# 5_SDRAM.net
KiCad netlist of a schematic drawn in Altium Designer
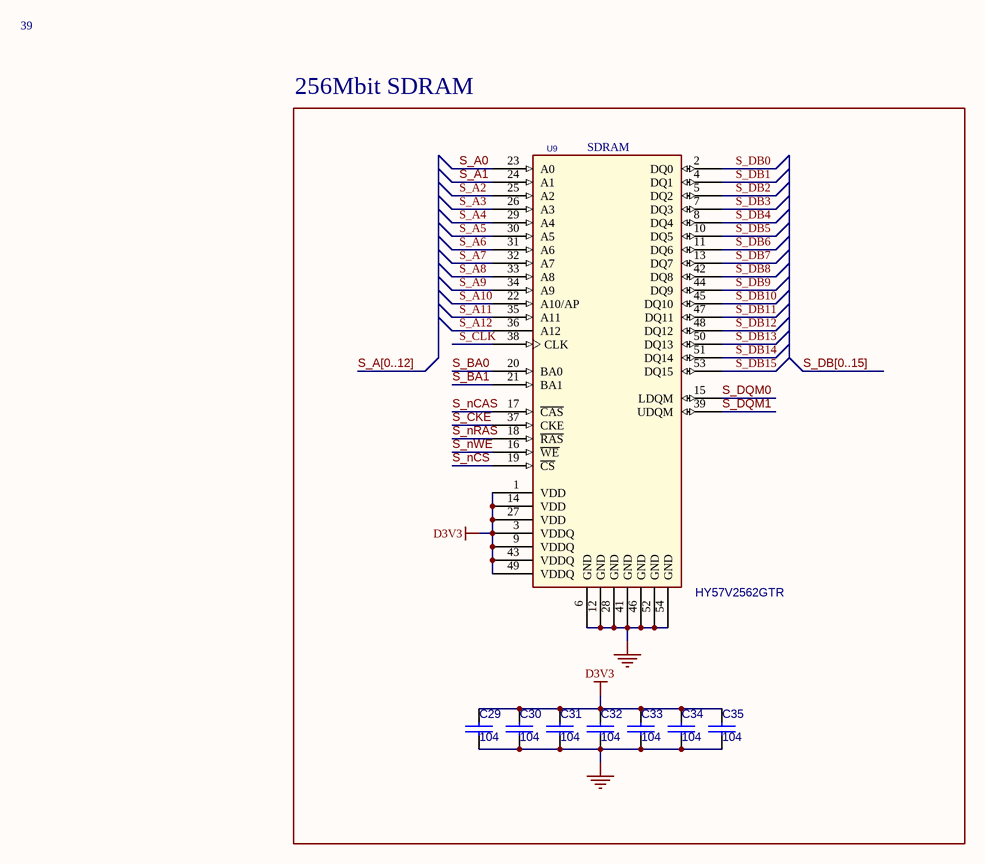
[diagram p0: 5_SDRAM.SchDoc]

(export (version "E")
  (design (tool "Eeschema 10.0.6"))
  (components
    (comp (ref "C29") (value "104") (libsource (lib "*") (part "C_Dup2")))
    (comp (ref "C30") (value "104") (libsource (lib "*") (part "C_Dup2")))
    (comp (ref "C31") (value "104") (libsource (lib "*") (part "C_Dup2")))
    (comp (ref "C32") (value "104") (libsource (lib "*") (part "C_Dup2")))
    (comp (ref "C33") (value "104") (libsource (lib "*") (part "C_Dup2")))
    (comp (ref "C34") (value "104") (libsource (lib "*") (part "C_Dup2")))
    (comp (ref "C35") (value "104") (libsource (lib "*") (part "C_Dup2")))
    (comp (ref "U9") (value "HY57V2562GTR") (libsource (lib "*") (part "HY57651620/SO_0")))
  )
  (nets
    (net (code "1") (name "/S_A0") (class "Default")
      (node (ref "U9") (pin "23") (pinfunction "A0_23") (pintype "input"))
    )
    (net (code "2") (name "/S_A1") (class "Default")
      (node (ref "U9") (pin "24") (pinfunction "A1_24") (pintype "input"))
    )
    (net (code "3") (name "/S_A2") (class "Default")
      (node (ref "U9") (pin "25") (pinfunction "A2_25") (pintype "input"))
    )
    (net (code "4") (name "/S_A3") (class "Default")
      (node (ref "U9") (pin "26") (pinfunction "A3_26") (pintype "input"))
    )
    (net (code "5") (name "/S_A4") (class "Default")
      (node (ref "U9") (pin "29") (pinfunction "A4_29") (pintype "input"))
    )
    (net (code "6") (name "/S_A5") (class "Default")
      (node (ref "U9") (pin "30") (pinfunction "A5_30") (pintype "input"))
    )
    (net (code "7") (name "/S_A6") (class "Default")
      (node (ref "U9") (pin "31") (pinfunction "A6_31") (pintype "input"))
    )
    (net (code "8") (name "/S_A7") (class "Default")
      (node (ref "U9") (pin "32") (pinfunction "A7_32") (pintype "input"))
    )
    (net (code "9") (name "/S_A8") (class "Default")
      (node (ref "U9") (pin "33") (pinfunction "A8_33") (pintype "input"))
    )
    (net (code "10") (name "/S_A9") (class "Default")
      (node (ref "U9") (pin "34") (pinfunction "A9_34") (pintype "input"))
    )
    (net (code "11") (name "/S_A10") (class "Default")
      (node (ref "U9") (pin "22") (pinfunction "A10/AP_22") (pintype "input"))
    )
    (net (code "12") (name "/S_A11") (class "Default")
      (node (ref "U9") (pin "35") (pinfunction "A11_35") (pintype "input"))
    )
    (net (code "13") (name "/S_A12") (class "Default")
      (node (ref "U9") (pin "36") (pinfunction "A12_36") (pintype "passive"))
    )
    (net (code "15") (name "/S_BA0") (class "Default")
      (node (ref "U9") (pin "20") (pinfunction "BA0_20") (pintype "input"))
    )
    (net (code "16") (name "/S_BA1") (class "Default")
      (node (ref "U9") (pin "21") (pinfunction "BA1_21") (pintype "input"))
    )
    (net (code "17") (name "/S_CKE") (class "Default")
      (node (ref "U9") (pin "37") (pinfunction "CKE_37") (pintype "input"))
    )
    (net (code "18") (name "/S_CLK") (class "Default")
      (node (ref "U9") (pin "38") (pinfunction "CLK_38") (pintype "input"))
    )
    (net (code "19") (name "/S_DB0") (class "Default")
      (node (ref "U9") (pin "2") (pinfunction "DQ0_2") (pintype "bidirectional"))
    )
    (net (code "20") (name "/S_DB1") (class "Default")
      (node (ref "U9") (pin "4") (pinfunction "DQ1_4") (pintype "bidirectional"))
    )
    (net (code "21") (name "/S_DB2") (class "Default")
      (node (ref "U9") (pin "5") (pinfunction "DQ2_5") (pintype "bidirectional"))
    )
    (net (code "22") (name "/S_DB3") (class "Default")
      (node (ref "U9") (pin "7") (pinfunction "DQ3_7") (pintype "bidirectional"))
    )
    (net (code "23") (name "/S_DB4") (class "Default")
      (node (ref "U9") (pin "8") (pinfunction "DQ4_8") (pintype "bidirectional"))
    )
    (net (code "24") (name "/S_DB5") (class "Default")
      (node (ref "U9") (pin "10") (pinfunction "DQ5_10") (pintype "bidirectional"))
    )
    (net (code "25") (name "/S_DB6") (class "Default")
      (node (ref "U9") (pin "11") (pinfunction "DQ6_11") (pintype "bidirectional"))
    )
    (net (code "26") (name "/S_DB7") (class "Default")
      (node (ref "U9") (pin "13") (pinfunction "DQ7_13") (pintype "bidirectional"))
    )
    (net (code "27") (name "/S_DB8") (class "Default")
      (node (ref "U9") (pin "42") (pinfunction "DQ8_42") (pintype "bidirectional"))
    )
    (net (code "28") (name "/S_DB9") (class "Default")
      (node (ref "U9") (pin "44") (pinfunction "DQ9_44") (pintype "bidirectional"))
    )
    (net (code "29") (name "/S_DB10") (class "Default")
      (node (ref "U9") (pin "45") (pinfunction "DQ10_45") (pintype "bidirectional"))
    )
    (net (code "30") (name "/S_DB11") (class "Default")
      (node (ref "U9") (pin "47") (pinfunction "DQ11_47") (pintype "bidirectional"))
    )
    (net (code "31") (name "/S_DB12") (class "Default")
      (node (ref "U9") (pin "48") (pinfunction "DQ12_48") (pintype "bidirectional"))
    )
    (net (code "32") (name "/S_DB13") (class "Default")
      (node (ref "U9") (pin "50") (pinfunction "DQ13_50") (pintype "bidirectional"))
    )
    (net (code "33") (name "/S_DB14") (class "Default")
      (node (ref "U9") (pin "51") (pinfunction "DQ14_51") (pintype "bidirectional"))
    )
    (net (code "34") (name "/S_DB15") (class "Default")
      (node (ref "U9") (pin "53") (pinfunction "DQ15_53") (pintype "bidirectional"))
    )
    (net (code "36") (name "/S_DQM0") (class "Default")
      (node (ref "U9") (pin "15") (pinfunction "LDQM_15") (pintype "bidirectional"))
    )
    (net (code "37") (name "/S_DQM1") (class "Default")
      (node (ref "U9") (pin "39") (pinfunction "UDQM_39") (pintype "bidirectional"))
    )
    (net (code "38") (name "/S_nCAS") (class "Default")
      (node (ref "U9") (pin "17") (pinfunction "~{CAS}_17") (pintype "input"))
    )
    (net (code "39") (name "/S_nCS") (class "Default")
      (node (ref "U9") (pin "19") (pinfunction "~{CS}_19") (pintype "input"))
    )
    (net (code "40") (name "/S_nRAS") (class "Default")
      (node (ref "U9") (pin "18") (pinfunction "~{RAS}_18") (pintype "input"))
    )
    (net (code "41") (name "/S_nWE") (class "Default")
      (node (ref "U9") (pin "16") (pinfunction "~{WE}_16") (pintype "input"))
    )
    (net (code "42") (name "D3V3") (class "Default")
      (node (ref "C29") (pin "1") (pinfunction "1_1") (pintype "passive"))
      (node (ref "C30") (pin "1") (pinfunction "1_1") (pintype "passive"))
      (node (ref "C31") (pin "1") (pinfunction "1_1") (pintype "passive"))
      (node (ref "C32") (pin "1") (pinfunction "1_1") (pintype "passive"))
      (node (ref "C33") (pin "1") (pinfunction "1_1") (pintype "passive"))
      (node (ref "C34") (pin "1") (pinfunction "1_1") (pintype "passive"))
      (node (ref "C35") (pin "1") (pinfunction "1_1") (pintype "passive"))
      (node (ref "U9") (pin "1") (pinfunction "VDD_1") (pintype "power_in"))
      (node (ref "U9") (pin "14") (pinfunction "VDD_14") (pintype "power_in"))
      (node (ref "U9") (pin "27") (pinfunction "VDD_27") (pintype "power_in"))
      (node (ref "U9") (pin "3") (pinfunction "VDDQ_3") (pintype "power_in"))
      (node (ref "U9") (pin "43") (pinfunction "VDDQ_43") (pintype "power_in"))
      (node (ref "U9") (pin "49") (pinfunction "VDDQ_49") (pintype "power_in"))
      (node (ref "U9") (pin "9") (pinfunction "VDDQ_9") (pintype "power_in"))
    )
    (net (code "43") (name "GND") (class "Default")
      (node (ref "C29") (pin "2") (pinfunction "2_2") (pintype "passive"))
      (node (ref "C30") (pin "2") (pinfunction "2_2") (pintype "passive"))
      (node (ref "C31") (pin "2") (pinfunction "2_2") (pintype "passive"))
      (node (ref "C32") (pin "2") (pinfunction "2_2") (pintype "passive"))
      (node (ref "C33") (pin "2") (pinfunction "2_2") (pintype "passive"))
      (node (ref "C34") (pin "2") (pinfunction "2_2") (pintype "passive"))
      (node (ref "C35") (pin "2") (pinfunction "2_2") (pintype "passive"))
      (node (ref "U9") (pin "12") (pinfunction "GND_12") (pintype "power_in"))
      (node (ref "U9") (pin "28") (pinfunction "GND_28") (pintype "power_in"))
      (node (ref "U9") (pin "41") (pinfunction "GND_41") (pintype "power_in"))
      (node (ref "U9") (pin "46") (pinfunction "GND_46") (pintype "power_in"))
      (node (ref "U9") (pin "52") (pinfunction "GND_52") (pintype "power_in"))
      (node (ref "U9") (pin "54") (pinfunction "GND_54") (pintype "power_in"))
      (node (ref "U9") (pin "6") (pinfunction "GND_6") (pintype "power_in"))
    )
  )
)
